# RF_Attenuator.net
KiCad netlist of a schematic drawn in Altium Designer
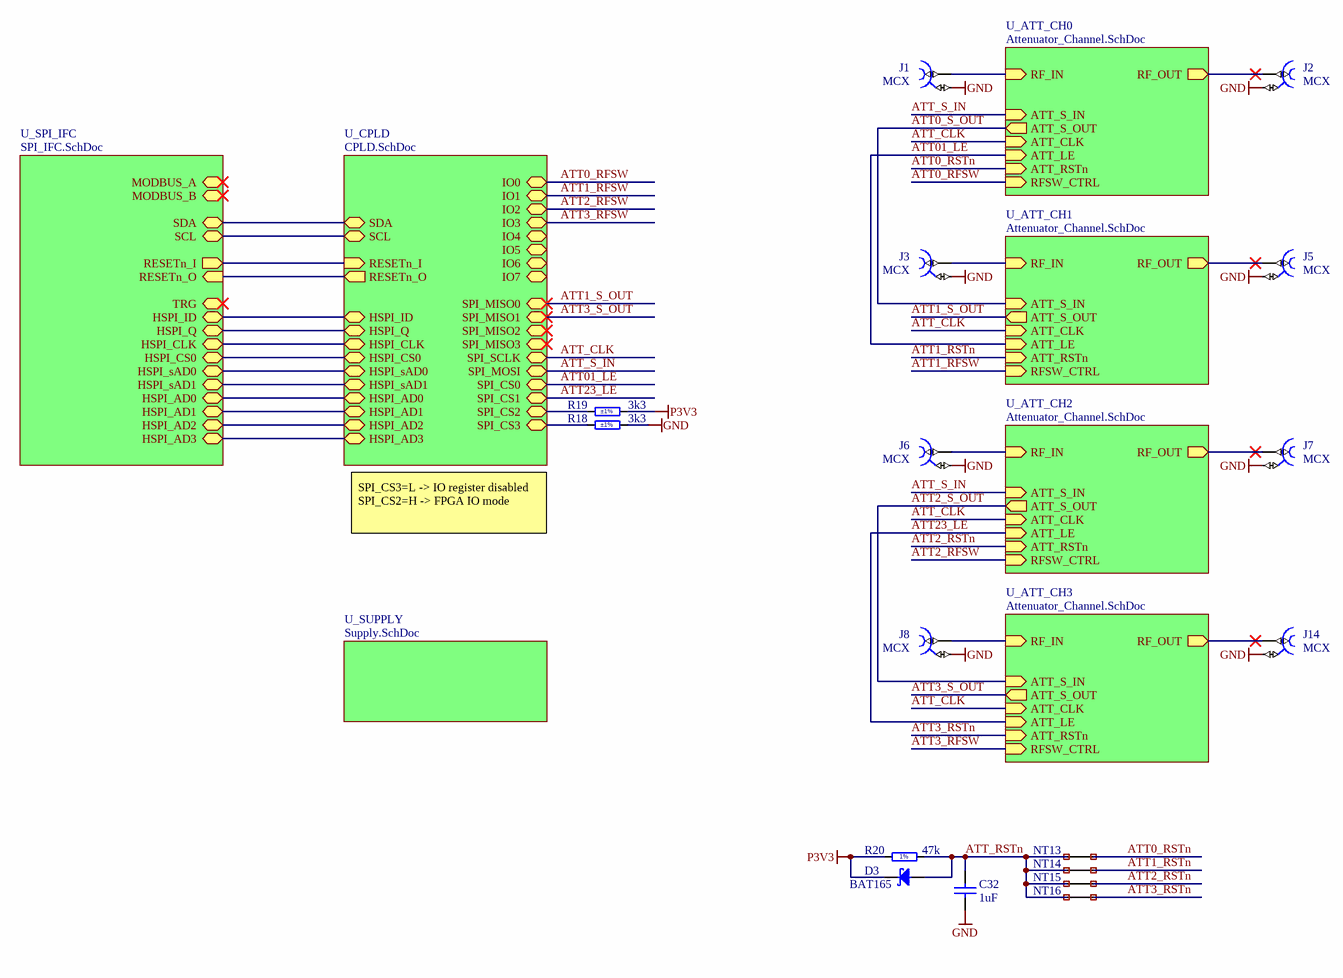
[diagram p0: RF_Attenuator.SchDoc]

(export (version "E")
  (design (tool "Eeschema 10.0.6"))
  (components
    (comp (ref "C32")
      (value "1uF")
      (footprint "CAPC1005X55N")
      (description "Non-polarised capacitor")
      (fields
        (field (name "PART NUMBER") "CC0402_1UF_16V_10%_X5R")
        (field (name "VOLTAGE") "16V")
        (field (name "AUTHOR") "CERN DEM JLC")
      )
      (libsource (lib "Capacitors") (part "Capacitor - non polarized"))
    )
    (comp (ref "D3")
      (value "BAT165")
      (footprint "SOD2512X110N")
      (description "Schottky Diode")
      (fields
        (field (name "VOLTAGE") "40V")
        (field (name "POWER") "750mA")
        (field (name "AUTHOR") "CERN DEM JLC")
      )
      (libsource (lib "ICs And Semiconductors") (part "Diode Schottky"))
    )
    (comp (ref "J1")
      (value "MCX")
      (footprint "AMPHENOL_919-109J-51PX")
      (fields
        (field (name "PART NUMBER") "AMPHENOL_919-109J-51PX")
        (field (name "MANUFACTURER") "AMPHENOL")
        (field (name "MANUFACTURER PART NUMBER") "919-109J-51PX (MCX6251B1-3GT30G-50)")
        (field (name "AUTHOR") "CERN DEM BC")
      )
      (libsource (lib "Connectors") (part "Coax_1Female_1Shield"))
    )
    (comp (ref "J2")
      (value "MCX")
      (footprint "AMPHENOL_919-109J-51PX")
      (fields
        (field (name "PART NUMBER") "AMPHENOL_919-109J-51PX")
        (field (name "MANUFACTURER") "AMPHENOL")
        (field (name "MANUFACTURER PART NUMBER") "919-109J-51PX (MCX6251B1-3GT30G-50)")
        (field (name "AUTHOR") "CERN DEM BC")
      )
      (libsource (lib "") (part "Coax_1Female_1Shield_1"))
    )
    (comp (ref "J3")
      (value "MCX")
      (footprint "AMPHENOL_919-109J-51PX")
      (fields
        (field (name "PART NUMBER") "AMPHENOL_919-109J-51PX")
        (field (name "MANUFACTURER") "AMPHENOL")
        (field (name "MANUFACTURER PART NUMBER") "919-109J-51PX (MCX6251B1-3GT30G-50)")
        (field (name "AUTHOR") "CERN DEM BC")
      )
      (libsource (lib "Connectors") (part "Coax_1Female_1Shield"))
    )
    (comp (ref "J5")
      (value "MCX")
      (footprint "AMPHENOL_919-109J-51PX")
      (fields
        (field (name "PART NUMBER") "AMPHENOL_919-109J-51PX")
        (field (name "MANUFACTURER") "AMPHENOL")
        (field (name "MANUFACTURER PART NUMBER") "919-109J-51PX (MCX6251B1-3GT30G-50)")
        (field (name "AUTHOR") "CERN DEM BC")
      )
      (libsource (lib "") (part "Coax_1Female_1Shield_1"))
    )
    (comp (ref "J6")
      (value "MCX")
      (footprint "AMPHENOL_919-109J-51PX")
      (fields
        (field (name "PART NUMBER") "AMPHENOL_919-109J-51PX")
        (field (name "MANUFACTURER") "AMPHENOL")
        (field (name "MANUFACTURER PART NUMBER") "919-109J-51PX (MCX6251B1-3GT30G-50)")
        (field (name "AUTHOR") "CERN DEM BC")
      )
      (libsource (lib "Connectors") (part "Coax_1Female_1Shield"))
    )
    (comp (ref "J7")
      (value "MCX")
      (footprint "AMPHENOL_919-109J-51PX")
      (fields
        (field (name "PART NUMBER") "AMPHENOL_919-109J-51PX")
        (field (name "MANUFACTURER") "AMPHENOL")
        (field (name "MANUFACTURER PART NUMBER") "919-109J-51PX (MCX6251B1-3GT30G-50)")
        (field (name "AUTHOR") "CERN DEM BC")
      )
      (libsource (lib "") (part "Coax_1Female_1Shield_1"))
    )
    (comp (ref "J8")
      (value "MCX")
      (footprint "AMPHENOL_919-109J-51PX")
      (fields
        (field (name "PART NUMBER") "AMPHENOL_919-109J-51PX")
        (field (name "MANUFACTURER") "AMPHENOL")
        (field (name "MANUFACTURER PART NUMBER") "919-109J-51PX (MCX6251B1-3GT30G-50)")
        (field (name "AUTHOR") "CERN DEM BC")
      )
      (libsource (lib "Connectors") (part "Coax_1Female_1Shield"))
    )
    (comp (ref "J14")
      (value "MCX")
      (footprint "AMPHENOL_919-109J-51PX")
      (fields
        (field (name "PART NUMBER") "AMPHENOL_919-109J-51PX")
        (field (name "MANUFACTURER") "AMPHENOL")
        (field (name "MANUFACTURER PART NUMBER") "919-109J-51PX (MCX6251B1-3GT30G-50)")
        (field (name "AUTHOR") "CERN DEM BC")
      )
      (libsource (lib "") (part "Coax_1Female_1Shield_1"))
    )
    (comp (ref "NT13")
      (value "Net Tie")
      (footprint "Net Tie 3")
      (fields (field (name "PART NUMBER") "Net Tie 3") (field (name "AUTHOR") "CERN DEM HF"))
      (libsource (lib "Eletro-mechanical") (part "Net Tie_a"))
    )
    (comp (ref "NT14")
      (value "Net Tie")
      (footprint "Net Tie 3")
      (fields (field (name "PART NUMBER") "Net Tie 3") (field (name "AUTHOR") "CERN DEM HF"))
      (libsource (lib "Eletro-mechanical") (part "Net Tie_a"))
    )
    (comp (ref "NT15")
      (value "Net Tie")
      (footprint "Net Tie 3")
      (fields (field (name "PART NUMBER") "Net Tie 3") (field (name "AUTHOR") "CERN DEM HF"))
      (libsource (lib "Eletro-mechanical") (part "Net Tie_a"))
    )
    (comp (ref "NT16")
      (value "Net Tie")
      (footprint "Net Tie 3")
      (fields (field (name "PART NUMBER") "Net Tie 3") (field (name "AUTHOR") "CERN DEM HF"))
      (libsource (lib "Eletro-mechanical") (part "Net Tie_a"))
    )
    (comp (ref "R18")
      (value "3k3")
      (footprint "RESC1005X40N")
      (description "Resistor - 1%")
      (fields
        (field (name "TOLERANCE") "±1%")
        (field (name "PART NUMBER") "R0402_3K3_1%_0.0625W_100PPM")
        (field (name "POWER") "0.0625W")
        (field (name "AUTHOR") "CERN DEM JLC")
      )
      (libsource (lib "Resistors") (part "Resistor - 1%"))
    )
    (comp (ref "R19")
      (value "3k3")
      (footprint "RESC1005X40N")
      (description "Resistor - 1%")
      (fields
        (field (name "TOLERANCE") "±1%")
        (field (name "PART NUMBER") "R0402_3K3_1%_0.0625W_100PPM")
        (field (name "POWER") "0.0625W")
        (field (name "AUTHOR") "CERN DEM JLC")
      )
      (libsource (lib "Resistors") (part "Resistor - 1%"))
    )
    (comp (ref "R20")
      (value "47k")
      (footprint "RESC1005X40N")
      (description "Resistor - 1%")
      (fields
        (field (name "PART NUMBER") "R0402_47K_1%_0.0625W_100PPM")
        (field (name "POWER") "0.0625W")
        (field (name "AUTHOR") "CERN DEM JLC")
      )
      (libsource (lib "Resistors") (part "Resistor - 1%"))
    )
  )
  (nets
    (net (code "2") (name "/ATT0_RSTn") (class "Default")
      (node (ref "NT13") (pin "2") (pinfunction "2_2") (pintype "bidirectional"))
    )
    (net (code "6") (name "/ATT1_RSTn") (class "Default")
      (node (ref "NT14") (pin "2") (pinfunction "2_2") (pintype "bidirectional"))
    )
    (net (code "9") (name "/ATT2_RSTn") (class "Default")
      (node (ref "NT15") (pin "2") (pinfunction "2_2") (pintype "bidirectional"))
    )
    (net (code "12") (name "/ATT3_RSTn") (class "Default")
      (node (ref "NT16") (pin "2") (pinfunction "2_2") (pintype "bidirectional"))
    )
    (net (code "16") (name "/ATT_RSTn") (class "Default")
      (node (ref "C32") (pin "2") (pinfunction "2_2") (pintype "passive"))
      (node (ref "D3") (pin "2") (pinfunction "A_2") (pintype "passive"))
      (node (ref "NT13") (pin "1") (pinfunction "1_1") (pintype "bidirectional"))
      (node (ref "NT14") (pin "1") (pinfunction "1_1") (pintype "bidirectional"))
      (node (ref "NT15") (pin "1") (pinfunction "1_1") (pintype "bidirectional"))
      (node (ref "NT16") (pin "1") (pinfunction "1_1") (pintype "bidirectional"))
      (node (ref "R20") (pin "2") (pinfunction "2_2") (pintype "passive"))
    )
    (net (code "36") (name "/RF_IN") (class "Default")
      (node (ref "J1") (pin "1") (pinfunction "1_1") (pintype "bidirectional"))
    )
    (net (code "37") (name "/RF_IN_1") (class "Default")
      (node (ref "J8") (pin "1") (pinfunction "1_1") (pintype "bidirectional"))
    )
    (net (code "38") (name "/RF_IN_2") (class "Default")
      (node (ref "J6") (pin "1") (pinfunction "1_1") (pintype "bidirectional"))
    )
    (net (code "39") (name "/RF_IN_3") (class "Default")
      (node (ref "J3") (pin "1") (pinfunction "1_1") (pintype "bidirectional"))
    )
    (net (code "40") (name "/RF_OUT") (class "Default")
      (node (ref "J7") (pin "1") (pinfunction "1_1") (pintype "bidirectional"))
    )
    (net (code "41") (name "/RF_OUT_1") (class "Default")
      (node (ref "J14") (pin "1") (pinfunction "1_1") (pintype "bidirectional"))
    )
    (net (code "42") (name "/RF_OUT_2") (class "Default")
      (node (ref "J2") (pin "1") (pinfunction "1_1") (pintype "bidirectional"))
    )
    (net (code "43") (name "/RF_OUT_3") (class "Default")
      (node (ref "J5") (pin "1") (pinfunction "1_1") (pintype "bidirectional"))
    )
    (net (code "46") (name "/SPI_CS2") (class "Default")
      (node (ref "R19") (pin "1") (pinfunction "1_1") (pintype "passive"))
    )
    (net (code "47") (name "/SPI_CS3") (class "Default")
      (node (ref "R18") (pin "1") (pinfunction "1_1") (pintype "passive"))
    )
    (net (code "51") (name "GND") (class "Default")
      (node (ref "C32") (pin "1") (pinfunction "1_1") (pintype "passive"))
      (node (ref "J1") (pin "2") (pinfunction "2_2") (pintype "bidirectional"))
      (node (ref "J14") (pin "2") (pinfunction "2_2") (pintype "bidirectional"))
      (node (ref "J2") (pin "2") (pinfunction "2_2") (pintype "bidirectional"))
      (node (ref "J3") (pin "2") (pinfunction "2_2") (pintype "bidirectional"))
      (node (ref "J5") (pin "2") (pinfunction "2_2") (pintype "bidirectional"))
      (node (ref "J6") (pin "2") (pinfunction "2_2") (pintype "bidirectional"))
      (node (ref "J7") (pin "2") (pinfunction "2_2") (pintype "bidirectional"))
      (node (ref "J8") (pin "2") (pinfunction "2_2") (pintype "bidirectional"))
      (node (ref "R18") (pin "2") (pinfunction "2_2") (pintype "passive"))
    )
    (net (code "52") (name "P3V3") (class "Default")
      (node (ref "D3") (pin "1") (pinfunction "C_1") (pintype "passive"))
      (node (ref "R19") (pin "2") (pinfunction "2_2") (pintype "passive"))
      (node (ref "R20") (pin "1") (pinfunction "1_1") (pintype "passive"))
    )
  )
)
